# pid_driver.net
KiCad netlist of a schematic drawn in EAGLE
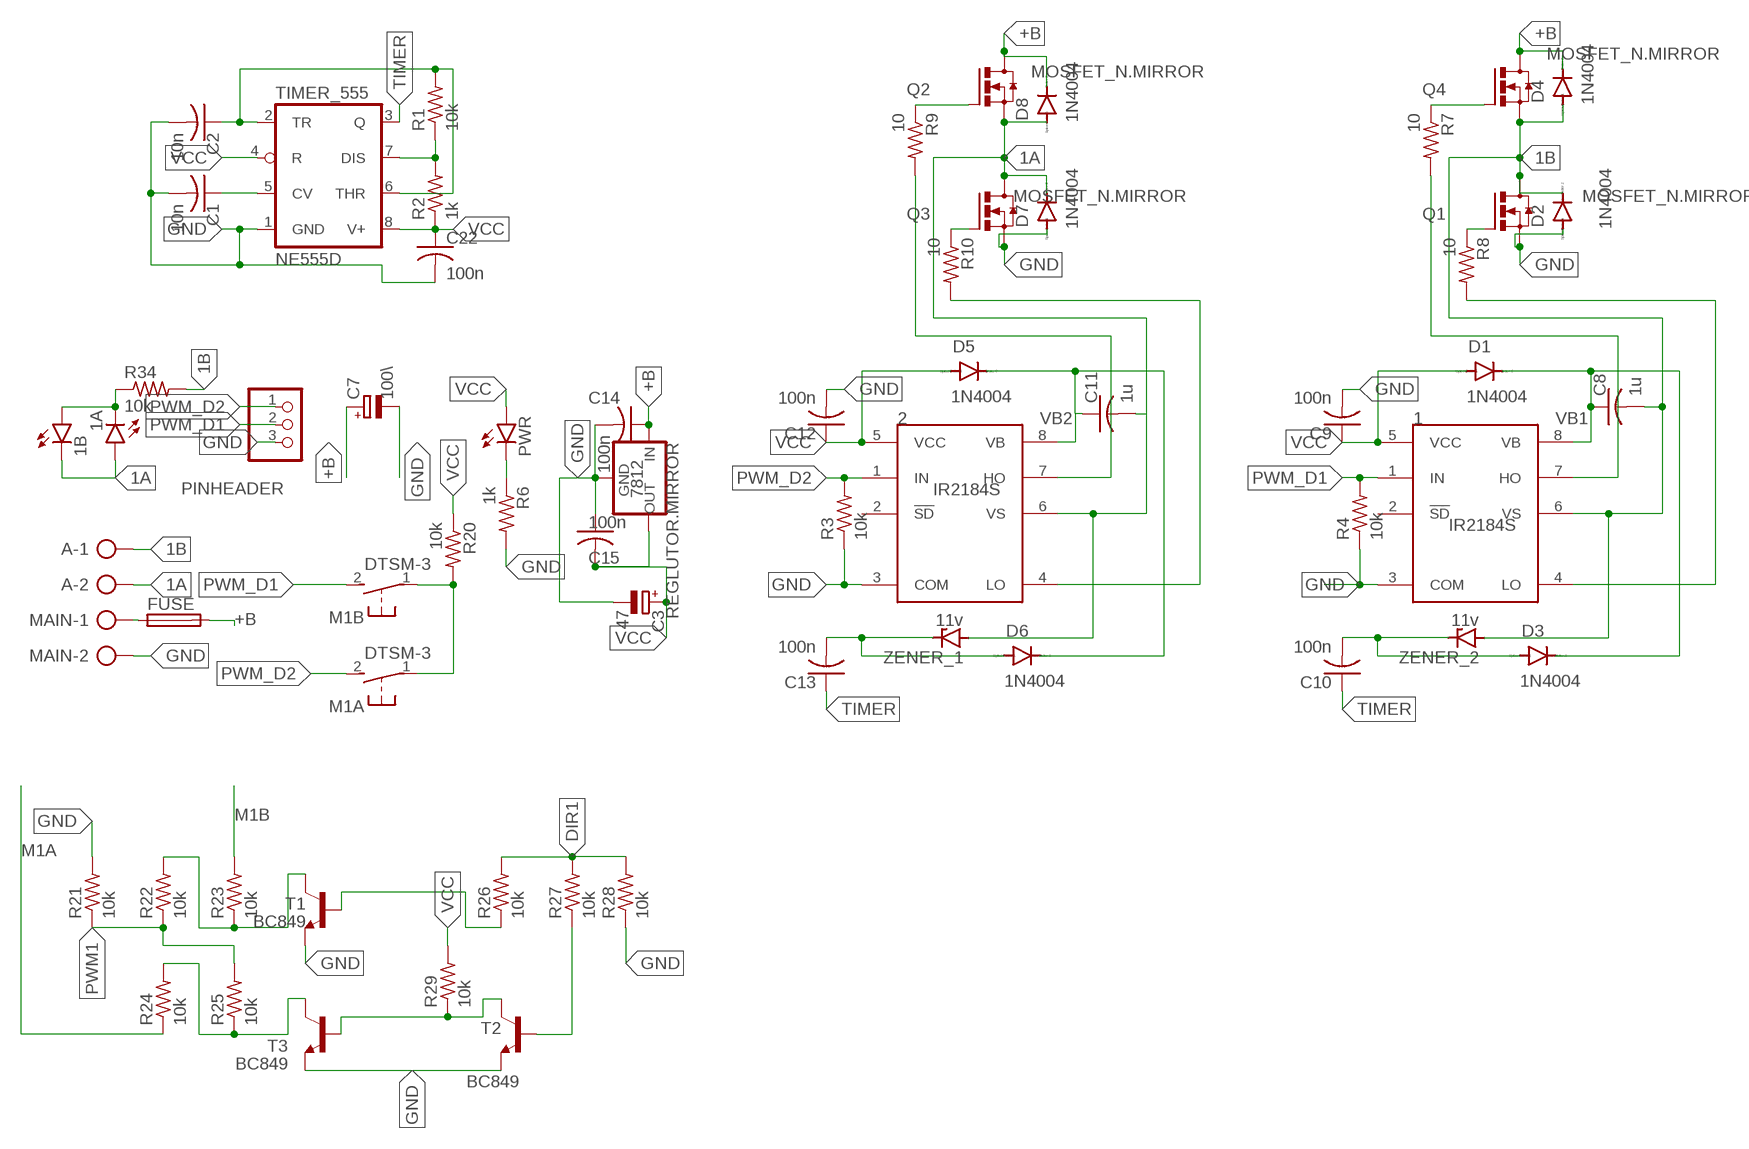
[diagram p0: schematic, sheet 1]
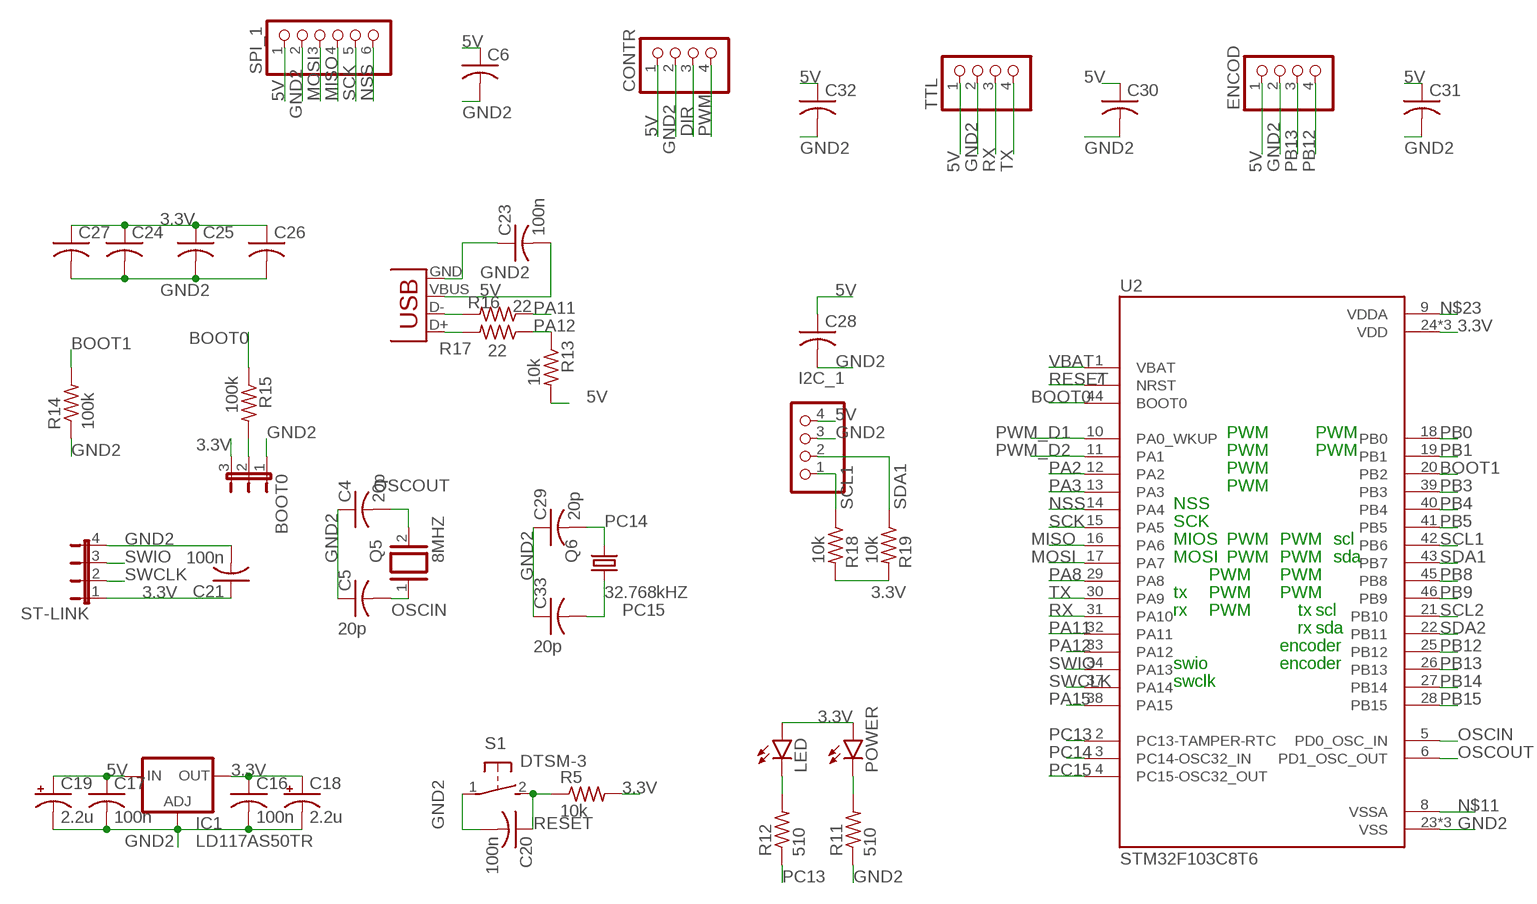
[diagram p1: schematic, sheet 2]

(export (version "E")
  (design (tool "Eeschema 10.0.6"))
  (components
    (comp (ref "BOOT0")
      (value "JP2E")
      (footprint "eagle-import:JP2")
      (libsource (lib "eagle-import") (part "JP2E"))
    )
    (comp (ref "C4")
      (value "20p")
      (footprint "eagle-import:C1206")
      (libsource (lib "eagle-import") (part "C-USC1206"))
    )
    (comp (ref "C5")
      (value "20p")
      (footprint "eagle-import:C1206")
      (libsource (lib "eagle-import") (part "C-USC1206"))
    )
    (comp (ref "C6")
      (value "C-USC1206")
      (footprint "eagle-import:C1206")
      (libsource (lib "eagle-import") (part "C-USC1206"))
    )
    (comp (ref "C16")
      (value "100n")
      (footprint "eagle-import:C1206")
      (libsource (lib "eagle-import") (part "C-USC1206"))
    )
    (comp (ref "C17")
      (value "100n")
      (footprint "eagle-import:C1206")
      (libsource (lib "eagle-import") (part "C-USC1206"))
    )
    (comp (ref "C18")
      (value "2.2u")
      (footprint "eagle-import:E2-5")
      (libsource (lib "eagle-import") (part "CPOL-USE2-5"))
    )
    (comp (ref "C19")
      (value "2.2u")
      (footprint "eagle-import:E2-5")
      (libsource (lib "eagle-import") (part "CPOL-USE2-5"))
    )
    (comp (ref "C20")
      (value "100n")
      (footprint "eagle-import:C1206")
      (libsource (lib "eagle-import") (part "C-USC1206"))
    )
    (comp (ref "C21")
      (value "100n")
      (footprint "eagle-import:C1206")
      (libsource (lib "eagle-import") (part "C-USC1206"))
    )
    (comp (ref "C23")
      (value "100n")
      (footprint "eagle-import:C1206")
      (libsource (lib "eagle-import") (part "C-USC1206"))
    )
    (comp (ref "C24")
      (value "C-USC1206")
      (footprint "eagle-import:C1206")
      (libsource (lib "eagle-import") (part "C-USC1206"))
    )
    (comp (ref "C25")
      (value "C-USC1206")
      (footprint "eagle-import:C1206")
      (libsource (lib "eagle-import") (part "C-USC1206"))
    )
    (comp (ref "C26")
      (value "C-USC1206")
      (footprint "eagle-import:C1206")
      (libsource (lib "eagle-import") (part "C-USC1206"))
    )
    (comp (ref "C27")
      (value "C-USC1206")
      (footprint "eagle-import:C1206")
      (libsource (lib "eagle-import") (part "C-USC1206"))
    )
    (comp (ref "C28")
      (value "C-USC1206")
      (footprint "eagle-import:C1206")
      (libsource (lib "eagle-import") (part "C-USC1206"))
    )
    (comp (ref "C29")
      (value "20p")
      (footprint "eagle-import:C1206")
      (libsource (lib "eagle-import") (part "C-USC1206"))
    )
    (comp (ref "C30")
      (value "C-USC1206")
      (footprint "eagle-import:C1206")
      (libsource (lib "eagle-import") (part "C-USC1206"))
    )
    (comp (ref "C31")
      (value "C-USC1206")
      (footprint "eagle-import:C1206")
      (libsource (lib "eagle-import") (part "C-USC1206"))
    )
    (comp (ref "C32")
      (value "C-USC1206")
      (footprint "eagle-import:C1206")
      (libsource (lib "eagle-import") (part "C-USC1206"))
    )
    (comp (ref "C33")
      (value "20p")
      (footprint "eagle-import:C1206")
      (libsource (lib "eagle-import") (part "C-USC1206"))
    )
    (comp (ref "CONTR")
      (value "PINHD-1X4")
      (footprint "eagle-import:1X04")
      (libsource (lib "eagle-import") (part "PINHD-1X4"))
    )
    (comp (ref "ENCOD")
      (value "PINHD-1X4")
      (footprint "eagle-import:1X04")
      (libsource (lib "eagle-import") (part "PINHD-1X4"))
    )
    (comp (ref "I2C_1")
      (value "PINHD-1X4")
      (footprint "eagle-import:1X04")
      (libsource (lib "eagle-import") (part "pinhead_325_PINHD-1X4"))
    )
    (comp (ref "IC1")
      (value "LD117AS50TR")
      (footprint "eagle-import:SOT223")
      (libsource (lib "eagle-import") (part "LD117A?S50TR"))
    )
    (comp (ref "LED")
      (value "LEDCHIPLED_1206")
      (footprint "eagle-import:CHIPLED_1206")
      (libsource (lib "eagle-import") (part "LEDCHIPLED_1206"))
    )
    (comp (ref "POWER")
      (value "LEDCHIPLED_1206")
      (footprint "eagle-import:CHIPLED_1206")
      (libsource (lib "eagle-import") (part "LEDCHIPLED_1206"))
    )
    (comp (ref "Q5")
      (value "8MHZ")
      (footprint "eagle-import:QS")
      (libsource (lib "eagle-import") (part "XTAL/S"))
    )
    (comp (ref "Q6")
      (value "32.768kHZ")
      (footprint "eagle-import:TC26H")
      (libsource (lib "eagle-import") (part "CRYSTALTC26H"))
    )
    (comp (ref "R5")
      (value "10k")
      (footprint "eagle-import:R1206")
      (libsource (lib "eagle-import") (part "R-US_R1206"))
    )
    (comp (ref "R11")
      (value "510")
      (footprint "eagle-import:R1206")
      (libsource (lib "eagle-import") (part "R-US_R1206"))
    )
    (comp (ref "R12")
      (value "510")
      (footprint "eagle-import:R1206")
      (libsource (lib "eagle-import") (part "R-US_R1206"))
    )
    (comp (ref "R13")
      (value "10k")
      (footprint "eagle-import:R1206")
      (libsource (lib "eagle-import") (part "R-US_R1206"))
    )
    (comp (ref "R14")
      (value "100k")
      (footprint "eagle-import:R1206")
      (libsource (lib "eagle-import") (part "R-US_R1206"))
    )
    (comp (ref "R15")
      (value "100k")
      (footprint "eagle-import:R1206")
      (libsource (lib "eagle-import") (part "R-US_R1206"))
    )
    (comp (ref "R16")
      (value "22")
      (footprint "eagle-import:R1206")
      (libsource (lib "eagle-import") (part "R-US_R1206"))
    )
    (comp (ref "R17")
      (value "22")
      (footprint "eagle-import:R1206")
      (libsource (lib "eagle-import") (part "R-US_R1206"))
    )
    (comp (ref "R18")
      (value "10k")
      (footprint "eagle-import:R1206")
      (libsource (lib "eagle-import") (part "R-US_R1206"))
    )
    (comp (ref "R19")
      (value "10k")
      (footprint "eagle-import:R1206")
      (libsource (lib "eagle-import") (part "R-US_R1206"))
    )
    (comp (ref "S1")
      (value "DTSM-3")
      (footprint "eagle-import:DTSM-3")
      (libsource (lib "eagle-import") (part "DTSM-3"))
    )
    (comp (ref "SPI_1")
      (value "PINHD-1X6")
      (footprint "eagle-import:1X06")
      (libsource (lib "eagle-import") (part "PINHD-1X6"))
    )
    (comp (ref "ST-LINK")
      (value "JP4E")
      (footprint "eagle-import:JP4")
      (libsource (lib "eagle-import") (part "JP4E"))
    )
    (comp (ref "TTL")
      (value "PINHD-1X4")
      (footprint "eagle-import:1X04")
      (libsource (lib "eagle-import") (part "PINHD-1X4"))
    )
    (comp (ref "U2")
      (value "STM32F103C8T6")
      (footprint "eagle-import:QFP50P900X900X160-48N")
      (fields (field (name "MF") "STMicroelectronics"))
      (libsource (lib "eagle-import") (part "STM32F103C8T6"))
    )
    (comp (ref "X1")
      (value "USB-MB-S")
      (footprint "eagle-import:USB-MB-S")
      (libsource (lib "eagle-import") (part "USB-MB-S"))
    )
    (comp (ref "1")
      (value "IR2184S")
      (footprint "eagle-import:SO08")
      (libsource (lib "eagle-import") (part "IR2184S"))
    )
    (comp (ref "1A")
      (value "LEDCHIPLED_1206")
      (footprint "eagle-import:CHIPLED_1206")
      (libsource (lib "eagle-import") (part "LEDCHIPLED_1206"))
    )
    (comp (ref "1B")
      (value "LEDCHIPLED_1206")
      (footprint "eagle-import:CHIPLED_1206")
      (libsource (lib "eagle-import") (part "LEDCHIPLED_1206"))
    )
    (comp (ref "2")
      (value "IR2184S")
      (footprint "eagle-import:SO08")
      (libsource (lib "eagle-import") (part "IR2184S"))
    )
    (comp (ref "7812")
      (value "REGLUTOR.MIRROR")
      (footprint "eagle-import:78XXL.MIRROR")
      (libsource (lib "eagle-import") (part "REGLUTOR.MIRROR"))
    )
    (comp (ref "A")
      (value "AK300/22")
      (footprint "eagle-import:XTALRR488W60L1090T465H350B")
      (libsource (lib "eagle-import") (part "AK300/22"))
    )
    (comp (ref "C1")
      (value "10n")
      (footprint "eagle-import:C1206K")
      (libsource (lib "eagle-import") (part "C-USC1206K"))
    )
    (comp (ref "C2")
      (value "10n")
      (footprint "eagle-import:C1206K")
      (libsource (lib "eagle-import") (part "C-USC1206K"))
    )
    (comp (ref "C3")
      (value "47")
      (footprint "eagle-import:E5-10,5")
      (libsource (lib "eagle-import") (part "CPOL-EUE5-10.5"))
    )
    (comp (ref "C7")
      (value "100\\")
      (footprint "eagle-import:E5-10,5")
      (libsource (lib "eagle-import") (part "CPOL-EUE5-10.5"))
    )
    (comp (ref "C8")
      (value "1u")
      (footprint "eagle-import:C1206K")
      (libsource (lib "eagle-import") (part "C-USC1206K"))
    )
    (comp (ref "C9")
      (value "100n")
      (footprint "eagle-import:C1206K")
      (libsource (lib "eagle-import") (part "C-USC1206K"))
    )
    (comp (ref "C10")
      (value "100n")
      (footprint "eagle-import:C1206K")
      (libsource (lib "eagle-import") (part "C-USC1206K"))
    )
    (comp (ref "C11")
      (value "1u")
      (footprint "eagle-import:C1206K")
      (libsource (lib "eagle-import") (part "C-USC1206K"))
    )
    (comp (ref "C12")
      (value "100n")
      (footprint "eagle-import:C1206K")
      (libsource (lib "eagle-import") (part "C-USC1206K"))
    )
    (comp (ref "C13")
      (value "100n")
      (footprint "eagle-import:C1206K")
      (libsource (lib "eagle-import") (part "C-USC1206K"))
    )
    (comp (ref "C14")
      (value "100n")
      (footprint "eagle-import:C1206K")
      (libsource (lib "eagle-import") (part "C-USC1206K"))
    )
    (comp (ref "C15")
      (value "100n")
      (footprint "eagle-import:C1206K")
      (libsource (lib "eagle-import") (part "C-USC1206K"))
    )
    (comp (ref "C22")
      (value "100n")
      (footprint "eagle-import:C1206K")
      (libsource (lib "eagle-import") (part "C-USC1206K"))
    )
    (comp (ref "D1")
      (value "1N4004")
      (footprint "eagle-import:DO41-10")
      (libsource (lib "eagle-import") (part "1N4004"))
    )
    (comp (ref "D2")
      (value "1N4004")
      (footprint "eagle-import:DO41-10")
      (libsource (lib "eagle-import") (part "1N4004"))
    )
    (comp (ref "D3")
      (value "1N4004")
      (footprint "eagle-import:DO41-10")
      (libsource (lib "eagle-import") (part "1N4004"))
    )
    (comp (ref "D4")
      (value "1N4004")
      (footprint "eagle-import:DO41-10")
      (libsource (lib "eagle-import") (part "1N4004"))
    )
    (comp (ref "D5")
      (value "1N4004")
      (footprint "eagle-import:DO41-10")
      (libsource (lib "eagle-import") (part "1N4004"))
    )
    (comp (ref "D6")
      (value "1N4004")
      (footprint "eagle-import:DO41-10")
      (libsource (lib "eagle-import") (part "1N4004"))
    )
    (comp (ref "D7")
      (value "1N4004")
      (footprint "eagle-import:DO41-10")
      (libsource (lib "eagle-import") (part "1N4004"))
    )
    (comp (ref "D8")
      (value "1N4004")
      (footprint "eagle-import:DO41-10")
      (libsource (lib "eagle-import") (part "1N4004"))
    )
    (comp (ref "FUSE")
      (value "FUSE_HOLDER")
      (footprint "eagle-import:SH22,5A")
      (libsource (lib "eagle-import") (part "FUSE_HOLDER"))
    )
    (comp (ref "M1A")
      (value "DTSM-3")
      (footprint "eagle-import:DTSM-3")
      (libsource (lib "eagle-import") (part "DTSM-3"))
    )
    (comp (ref "M1B")
      (value "DTSM-3")
      (footprint "eagle-import:DTSM-3")
      (libsource (lib "eagle-import") (part "DTSM-3"))
    )
    (comp (ref "MAIN")
      (value "AK300/22")
      (footprint "eagle-import:XTALRR488W60L1090T465H350B")
      (libsource (lib "eagle-import") (part "AK300/22"))
    )
    (comp (ref "PINHEADER")
      (value "PINHD-1X3")
      (footprint "eagle-import:1X03")
      (libsource (lib "eagle-import") (part "PINHD-1X3"))
    )
    (comp (ref "PWR")
      (value "LEDCHIPLED_1206")
      (footprint "eagle-import:CHIPLED_1206")
      (libsource (lib "eagle-import") (part "LEDCHIPLED_1206"))
    )
    (comp (ref "Q1")
      (value "MOSFET_N.MIRROR")
      (footprint "eagle-import:TO220.MIRROR")
      (libsource (lib "eagle-import") (part "MOSFET_N.MIRROR"))
    )
    (comp (ref "Q2")
      (value "MOSFET_N.MIRROR")
      (footprint "eagle-import:TO220.MIRROR")
      (libsource (lib "eagle-import") (part "MOSFET_N.MIRROR"))
    )
    (comp (ref "Q3")
      (value "MOSFET_N.MIRROR")
      (footprint "eagle-import:TO220.MIRROR")
      (libsource (lib "eagle-import") (part "MOSFET_N.MIRROR"))
    )
    (comp (ref "Q4")
      (value "MOSFET_N.MIRROR")
      (footprint "eagle-import:TO220.MIRROR")
      (libsource (lib "eagle-import") (part "MOSFET_N.MIRROR"))
    )
    (comp (ref "R1")
      (value "10k")
      (footprint "eagle-import:M1206")
      (libsource (lib "eagle-import") (part "R-US_M1206"))
    )
    (comp (ref "R2")
      (value "1k")
      (footprint "eagle-import:M1206")
      (libsource (lib "eagle-import") (part "R-US_M1206"))
    )
    (comp (ref "R3")
      (value "10k")
      (footprint "eagle-import:M1206")
      (libsource (lib "eagle-import") (part "R-US_M1206"))
    )
    (comp (ref "R4")
      (value "10k")
      (footprint "eagle-import:M1206")
      (libsource (lib "eagle-import") (part "R-US_M1206"))
    )
    (comp (ref "R6")
      (value "1k")
      (footprint "eagle-import:M1206")
      (libsource (lib "eagle-import") (part "R-US_M1206"))
    )
    (comp (ref "R7")
      (value "10")
      (footprint "eagle-import:M1206")
      (libsource (lib "eagle-import") (part "R-US_M1206"))
    )
    (comp (ref "R8")
      (value "10")
      (footprint "eagle-import:M1206")
      (libsource (lib "eagle-import") (part "R-US_M1206"))
    )
    (comp (ref "R9")
      (value "10")
      (footprint "eagle-import:M1206")
      (libsource (lib "eagle-import") (part "R-US_M1206"))
    )
    (comp (ref "R10")
      (value "10")
      (footprint "eagle-import:M1206")
      (libsource (lib "eagle-import") (part "R-US_M1206"))
    )
    (comp (ref "R20")
      (value "10k")
      (footprint "eagle-import:M1206")
      (libsource (lib "eagle-import") (part "R-US_M1206"))
    )
    (comp (ref "R21")
      (value "10k")
      (footprint "eagle-import:R1206")
      (libsource (lib "eagle-import") (part "R-US_R1206"))
    )
    (comp (ref "R22")
      (value "10k")
      (footprint "eagle-import:R1206")
      (libsource (lib "eagle-import") (part "R-US_R1206"))
    )
    (comp (ref "R23")
      (value "10k")
      (footprint "eagle-import:R1206")
      (libsource (lib "eagle-import") (part "R-US_R1206"))
    )
    (comp (ref "R24")
      (value "10k")
      (footprint "eagle-import:R1206")
      (libsource (lib "eagle-import") (part "R-US_R1206"))
    )
    (comp (ref "R25")
      (value "10k")
      (footprint "eagle-import:R1206")
      (libsource (lib "eagle-import") (part "R-US_R1206"))
    )
    (comp (ref "R26")
      (value "10k")
      (footprint "eagle-import:R1206")
      (libsource (lib "eagle-import") (part "R-US_R1206"))
    )
    (comp (ref "R27")
      (value "10k")
      (footprint "eagle-import:R1206")
      (libsource (lib "eagle-import") (part "R-US_R1206"))
    )
    (comp (ref "R28")
      (value "10k")
      (footprint "eagle-import:R1206")
      (libsource (lib "eagle-import") (part "R-US_R1206"))
    )
    (comp (ref "R29")
      (value "10k")
      (footprint "eagle-import:R1206")
      (libsource (lib "eagle-import") (part "R-US_R1206"))
    )
    (comp (ref "R34")
      (value "10k")
      (footprint "eagle-import:M1206")
      (libsource (lib "eagle-import") (part "R-US_M1206"))
    )
    (comp (ref "T1")
      (value "BC849")
      (footprint "eagle-import:SOT23")
      (libsource (lib "eagle-import") (part "BC849"))
    )
    (comp (ref "T2")
      (value "BC849")
      (footprint "eagle-import:SOT23")
      (libsource (lib "eagle-import") (part "BC849"))
    )
    (comp (ref "T3")
      (value "BC849")
      (footprint "eagle-import:SOT23")
      (libsource (lib "eagle-import") (part "BC849"))
    )
    (comp (ref "TIMER_555")
      (value "NE555D")
      (footprint "eagle-import:SO08")
      (libsource (lib "eagle-import") (part "555DNE"))
    )
    (comp (ref "ZENER_1")
      (value "11v")
      (footprint "eagle-import:SOD81")
      (libsource (lib "eagle-import") (part "BZD23"))
    )
    (comp (ref "ZENER_2")
      (value "11v")
      (footprint "eagle-import:SOD81")
      (libsource (lib "eagle-import") (part "BZD23"))
    )
  )
  (nets
    (net (code "1") (name "+B") (class "Default")
      (node (ref "7812") (pin "IN") (pinfunction "IN_IN") (pintype "input"))
      (node (ref "C14") (pin "1") (pinfunction "1_1") (pintype "passive"))
      (node (ref "C7") (pin "+") (pinfunction "+_+") (pintype "passive"))
      (node (ref "D4") (pin "C") (pinfunction "C_C") (pintype "passive"))
      (node (ref "D8") (pin "C") (pinfunction "C_C") (pintype "passive"))
      (node (ref "FUSE") (pin "2") (pinfunction "2_2") (pintype "passive"))
      (node (ref "Q2") (pin "D") (pinfunction "D_D") (pintype "passive"))
      (node (ref "Q4") (pin "D") (pinfunction "D_D") (pintype "passive"))
    )
    (net (code "2") (name "1A") (class "Default")
      (node (ref "1A") (pin "A") (pinfunction "A_A") (pintype "passive"))
      (node (ref "1B") (pin "C") (pinfunction "C_C") (pintype "passive"))
      (node (ref "2") (pin "6") (pinfunction "VS_6") (pintype "power_in"))
      (node (ref "A") (pin "2") (pinfunction "KL_2") (pintype "passive"))
      (node (ref "C11") (pin "2") (pinfunction "2_2") (pintype "passive"))
      (node (ref "D7") (pin "C") (pinfunction "C_C") (pintype "passive"))
      (node (ref "D8") (pin "A") (pinfunction "A_A") (pintype "passive"))
      (node (ref "Q2") (pin "S") (pinfunction "S_S") (pintype "passive"))
      (node (ref "Q3") (pin "D") (pinfunction "D_D") (pintype "passive"))
      (node (ref "ZENER_1") (pin "A") (pinfunction "A_A") (pintype "passive"))
    )
    (net (code "3") (name "1B") (class "Default")
      (node (ref "1") (pin "6") (pinfunction "VS_6") (pintype "power_in"))
      (node (ref "A") (pin "1") (pinfunction "KL_1") (pintype "passive"))
      (node (ref "C8") (pin "2") (pinfunction "2_2") (pintype "passive"))
      (node (ref "D2") (pin "C") (pinfunction "C_C") (pintype "passive"))
      (node (ref "D4") (pin "A") (pinfunction "A_A") (pintype "passive"))
      (node (ref "Q1") (pin "D") (pinfunction "D_D") (pintype "passive"))
      (node (ref "Q4") (pin "S") (pinfunction "S_S") (pintype "passive"))
      (node (ref "R34") (pin "2") (pinfunction "2_2") (pintype "passive"))
      (node (ref "ZENER_2") (pin "A") (pinfunction "A_A") (pintype "passive"))
    )
    (net (code "4") (name "3.3V") (class "Default")
      (node (ref "BOOT0") (pin "3") (pinfunction "3_3") (pintype "passive"))
      (node (ref "C16") (pin "1") (pinfunction "1_1") (pintype "passive"))
      (node (ref "C18") (pin "+") (pinfunction "+_+") (pintype "passive"))
      (node (ref "C21") (pin "1") (pinfunction "1_1") (pintype "passive"))
      (node (ref "C24") (pin "1") (pinfunction "1_1") (pintype "passive"))
      (node (ref "C25") (pin "1") (pinfunction "1_1") (pintype "passive"))
      (node (ref "C26") (pin "1") (pinfunction "1_1") (pintype "passive"))
      (node (ref "C27") (pin "1") (pinfunction "1_1") (pintype "passive"))
      (node (ref "IC1") (pin "4") (pinfunction "OUT_4") (pintype "passive"))
      (node (ref "LED") (pin "A") (pinfunction "A_A") (pintype "passive"))
      (node (ref "POWER") (pin "A") (pinfunction "A_A") (pintype "passive"))
      (node (ref "R18") (pin "2") (pinfunction "2_2") (pintype "passive"))
      (node (ref "R19") (pin "2") (pinfunction "2_2") (pintype "passive"))
      (node (ref "R5") (pin "2") (pinfunction "2_2") (pintype "passive"))
      (node (ref "ST-LINK") (pin "1") (pinfunction "1_1") (pintype "passive"))
      (node (ref "U2") (pin "24") (pinfunction "VDD_24") (pintype "power_in"))
      (node (ref "U2") (pin "36") (pinfunction "VDD_36") (pintype "power_in"))
      (node (ref "U2") (pin "48") (pinfunction "VDD_48") (pintype "power_in"))
    )
    (net (code "5") (name "5V") (class "Default")
      (node (ref "C17") (pin "1") (pinfunction "1_1") (pintype "passive"))
      (node (ref "C19") (pin "+") (pinfunction "+_+") (pintype "passive"))
      (node (ref "C23") (pin "2") (pinfunction "2_2") (pintype "passive"))
      (node (ref "C28") (pin "1") (pinfunction "1_1") (pintype "passive"))
      (node (ref "C30") (pin "1") (pinfunction "1_1") (pintype "passive"))
      (node (ref "C31") (pin "1") (pinfunction "1_1") (pintype "passive"))
      (node (ref "C32") (pin "1") (pinfunction "1_1") (pintype "passive"))
      (node (ref "C6") (pin "1") (pinfunction "1_1") (pintype "passive"))
      (node (ref "CONTR") (pin "1") (pinfunction "1_1") (pintype "passive"))
      (node (ref "ENCOD") (pin "1") (pinfunction "1_1") (pintype "passive"))
      (node (ref "I2C_1") (pin "4") (pinfunction "4_4") (pintype "passive"))
      (node (ref "IC1") (pin "3") (pinfunction "IN_3") (pintype "input"))
      (node (ref "R13") (pin "2") (pinfunction "2_2") (pintype "passive"))
      (node (ref "SPI_1") (pin "1") (pinfunction "1_1") (pintype "passive"))
      (node (ref "TTL") (pin "1") (pinfunction "1_1") (pintype "passive"))
      (node (ref "X1") (pin "VBUS") (pinfunction "VBUS_VBUS") (pintype "bidirectional"))
    )
    (net (code "6") (name "BOOT0") (class "Default")
      (node (ref "R15") (pin "1") (pinfunction "1_1") (pintype "passive"))
      (node (ref "U2") (pin "44") (pinfunction "BOOT0_44") (pintype "input"))
    )
    (net (code "7") (name "BOOT1") (class "Default")
      (node (ref "R14") (pin "2") (pinfunction "2_2") (pintype "passive"))
      (node (ref "U2") (pin "20") (pinfunction "PB2_20") (pintype "bidirectional"))
    )
    (net (code "8") (name "DIR") (class "Default")
      (node (ref "CONTR") (pin "3") (pinfunction "3_3") (pintype "passive"))
    )
    (net (code "9") (name "DIR1") (class "Default")
      (node (ref "R26") (pin "2") (pinfunction "2_2") (pintype "passive"))
      (node (ref "R27") (pin "2") (pinfunction "2_2") (pintype "passive"))
      (node (ref "R28") (pin "2") (pinfunction "2_2") (pintype "passive"))
    )
    (net (code "10") (name "GND") (class "Default")
      (node (ref "1") (pin "3") (pinfunction "COM_3") (pintype "power_in"))
      (node (ref "2") (pin "3") (pinfunction "COM_3") (pintype "power_in"))
      (node (ref "7812") (pin "GND") (pinfunction "GND_GND") (pintype "input"))
      (node (ref "C1") (pin "2") (pinfunction "2_2") (pintype "passive"))
      (node (ref "C12") (pin "2") (pinfunction "2_2") (pintype "passive"))
      (node (ref "C14") (pin "2") (pinfunction "2_2") (pintype "passive"))
      (node (ref "C15") (pin "1") (pinfunction "1_1") (pintype "passive"))
      (node (ref "C2") (pin "2") (pinfunction "2_2") (pintype "passive"))
      (node (ref "C22") (pin "2") (pinfunction "2_2") (pintype "passive"))
      (node (ref "C3") (pin "-") (pinfunction "-_-") (pintype "passive"))
      (node (ref "C7") (pin "-") (pinfunction "-_-") (pintype "passive"))
      (node (ref "C9") (pin "2") (pinfunction "2_2") (pintype "passive"))
      (node (ref "D2") (pin "A") (pinfunction "A_A") (pintype "passive"))
      (node (ref "D7") (pin "A") (pinfunction "A_A") (pintype "passive"))
      (node (ref "MAIN") (pin "2") (pinfunction "KL_2") (pintype "passive"))
      (node (ref "PINHEADER") (pin "3") (pinfunction "3_3") (pintype "passive"))
      (node (ref "Q1") (pin "S") (pinfunction "S_S") (pintype "passive"))
      (node (ref "Q3") (pin "S") (pinfunction "S_S") (pintype "passive"))
      (node (ref "R21") (pin "2") (pinfunction "2_2") (pintype "passive"))
      (node (ref "R28") (pin "1") (pinfunction "1_1") (pintype "passive"))
      (node (ref "R3") (pin "1") (pinfunction "1_1") (pintype "passive"))
      (node (ref "R4") (pin "1") (pinfunction "1_1") (pintype "passive"))
      (node (ref "R6") (pin "2") (pinfunction "2_2") (pintype "passive"))
      (node (ref "T1") (pin "2") (pinfunction "E_2") (pintype "passive"))
      (node (ref "T2") (pin "2") (pinfunction "E_2") (pintype "passive"))
      (node (ref "T3") (pin "2") (pinfunction "E_2") (pintype "passive"))
      (node (ref "TIMER_555") (pin "1") (pinfunction "GND_1") (pintype "power_in"))
    )
    (net (code "11") (name "GND2") (class "Default")
      (node (ref "BOOT0") (pin "1") (pinfunction "1_1") (pintype "passive"))
      (node (ref "C16") (pin "2") (pinfunction "2_2") (pintype "passive"))
      (node (ref "C17") (pin "2") (pinfunction "2_2") (pintype "passive"))
      (node (ref "C18") (pin "-") (pinfunction "-_-") (pintype "passive"))
      (node (ref "C19") (pin "-") (pinfunction "-_-") (pintype "passive"))
      (node (ref "C20") (pin "2") (pinfunction "2_2") (pintype "passive"))
      (node (ref "C21") (pin "2") (pinfunction "2_2") (pintype "passive"))
      (node (ref "C23") (pin "1") (pinfunction "1_1") (pintype "passive"))
      (node (ref "C24") (pin "2") (pinfunction "2_2") (pintype "passive"))
      (node (ref "C25") (pin "2") (pinfunction "2_2") (pintype "passive"))
      (node (ref "C26") (pin "2") (pinfunction "2_2") (pintype "passive"))
      (node (ref "C27") (pin "2") (pinfunction "2_2") (pintype "passive"))
      (node (ref "C28") (pin "2") (pinfunction "2_2") (pintype "passive"))
      (node (ref "C29") (pin "1") (pinfunction "1_1") (pintype "passive"))
      (node (ref "C30") (pin "2") (pinfunction "2_2") (pintype "passive"))
      (node (ref "C31") (pin "2") (pinfunction "2_2") (pintype "passive"))
      (node (ref "C32") (pin "2") (pinfunction "2_2") (pintype "passive"))
      (node (ref "C33") (pin "1") (pinfunction "1_1") (pintype "passive"))
      (node (ref "C4") (pin "1") (pinfunction "1_1") (pintype "passive"))
      (node (ref "C5") (pin "1") (pinfunction "1_1") (pintype "passive"))
      (node (ref "C6") (pin "2") (pinfunction "2_2") (pintype "passive"))
      (node (ref "CONTR") (pin "2") (pinfunction "2_2") (pintype "passive"))
      (node (ref "ENCOD") (pin "2") (pinfunction "2_2") (pintype "passive"))
      (node (ref "I2C_1") (pin "3") (pinfunction "3_3") (pintype "passive"))
      (node (ref "IC1") (pin "1") (pinfunction "ADJ_1") (pintype "input"))
      (node (ref "R11") (pin "1") (pinfunction "1_1") (pintype "passive"))
      (node (ref "R14") (pin "1") (pinfunction "1_1") (pintype "passive"))
      (node (ref "S1") (pin "1") (pinfunction "1_1") (pintype "passive"))
      (node (ref "SPI_1") (pin "2") (pinfunction "2_2") (pintype "passive"))
      (node (ref "ST-LINK") (pin "4") (pinfunction "4_4") (pintype "passive"))
      (node (ref "TTL") (pin "2") (pinfunction "2_2") (pintype "passive"))
      (node (ref "U2") (pin "23") (pinfunction "VSS_23") (pintype "power_in"))
      (node (ref "U2") (pin "35") (pinfunction "VSS_35") (pintype "power_in"))
      (node (ref "U2") (pin "47") (pinfunction "VSS_47") (pintype "power_in"))
      (node (ref "X1") (pin "GND") (pinfunction "GND_GND") (pintype "bidirectional"))
    )
    (net (code "12") (name "M1A") (class "Default")
      (node (ref "R24") (pin "1") (pinfunction "1_1") (pintype "passive"))
    )
    (net (code "13") (name "M1B") (class "Default")
      (node (ref "R23") (pin "2") (pinfunction "2_2") (pintype "passive"))
    )
    (net (code "14") (name "MISO") (class "Default")
      (node (ref "SPI_1") (pin "4") (pinfunction "4_4") (pintype "passive"))
      (node (ref "U2") (pin "16") (pinfunction "PA6_16") (pintype "bidirectional"))
    )
    (net (code "15") (name "MOSI") (class "Default")
      (node (ref "SPI_1") (pin "3") (pinfunction "3_3") (pintype "passive"))
      (node (ref "U2") (pin "17") (pinfunction "PA7_17") (pintype "bidirectional"))
    )
    (net (code "16") (name "N$11") (class "Default")
      (node (ref "U2") (pin "8") (pinfunction "VSSA_8") (pintype "power_in"))
    )
    (net (code "17") (name "N$23") (class "Default")
      (node (ref "U2") (pin "9") (pinfunction "VDDA_9") (pintype "power_in"))
    )
    (net (code "18") (name "NSS") (class "Default")
      (node (ref "SPI_1") (pin "6") (pinfunction "6_6") (pintype "passive"))
      (node (ref "U2") (pin "14") (pinfunction "PA4_14") (pintype "bidirectional"))
    )
    (net (code "19") (name "Net-(1-HO)") (class "Default")
      (node (ref "1") (pin "7") (pinfunction "HO_7") (pintype "output"))
      (node (ref "R7") (pin "2") (pinfunction "2_2") (pintype "passive"))
    )
    (net (code "20") (name "Net-(1-LO)") (class "Default")
      (node (ref "1") (pin "4") (pinfunction "LO_4") (pintype "output"))
      (node (ref "R8") (pin "2") (pinfunction "2_2") (pintype "passive"))
    )
    (net (code "21") (name "Net-(1A-PadC)") (class "Default")
      (node (ref "1A") (pin "C") (pinfunction "C_C") (pintype "passive"))
      (node (ref "1B") (pin "A") (pinfunction "A_A") (pintype "passive"))
      (node (ref "R34") (pin "1") (pinfunction "1_1") (pintype "passive"))
    )
    (net (code "22") (name "Net-(2-HO)") (class "Default")
      (node (ref "2") (pin "7") (pinfunction "HO_7") (pintype "output"))
      (node (ref "R9") (pin "2") (pinfunction "2_2") (pintype "passive"))
    )
    (net (code "23") (name "Net-(2-LO)") (class "Default")
      (node (ref "2") (pin "4") (pinfunction "LO_4") (pintype "output"))
      (node (ref "R10") (pin "2") (pinfunction "2_2") (pintype "passive"))
    )
    (net (code "24") (name "Net-(BOOT0-Pad2)") (class "Default")
      (node (ref "BOOT0") (pin "2") (pinfunction "2_2") (pintype "passive"))
      (node (ref "R15") (pin "2") (pinfunction "2_2") (pintype "passive"))
    )
    (net (code "25") (name "Net-(C10-Pad2)") (class "Default")
      (node (ref "C10") (pin "2") (pinfunction "2_2") (pintype "passive"))
      (node (ref "D3") (pin "A") (pinfunction "A_A") (pintype "passive"))
      (node (ref "ZENER_2") (pin "C") (pinfunction "C_C") (pintype "passive"))
    )
    (net (code "26") (name "Net-(C13-Pad2)") (class "Default")
      (node (ref "C13") (pin "2") (pinfunction "2_2") (pintype "passive"))
      (node (ref "D6") (pin "A") (pinfunction "A_A") (pintype "passive"))
      (node (ref "ZENER_1") (pin "C") (pinfunction "C_C") (pintype "passive"))
    )
    (net (code "27") (name "Net-(LED-PadC)") (class "Default")
      (node (ref "LED") (pin "C") (pinfunction "C_C") (pintype "passive"))
      (node (ref "R12") (pin "2") (pinfunction "2_2") (pintype "passive"))
    )
    (net (code "28") (name "Net-(M1A-Pad1)") (class "Default")
      (node (ref "M1A") (pin "1") (pinfunction "1_1") (pintype "passive"))
      (node (ref "M1B") (pin "1") (pinfunction "1_1") (pintype "passive"))
      (node (ref "R20") (pin "2") (pinfunction "2_2") (pintype "passive"))
    )
    (net (code "29") (name "Net-(MAINA-KL)") (class "Default")
      (node (ref "FUSE") (pin "1") (pinfunction "1_1") (pintype "passive"))
      (node (ref "MAIN") (pin "1") (pinfunction "KL_1") (pintype "passive"))
    )
    (net (code "30") (name "Net-(POWER-PadC)") (class "Default")
      (node (ref "POWER") (pin "C") (pinfunction "C_C") (pintype "passive"))
      (node (ref "R11") (pin "2") (pinfunction "2_2") (pintype "passive"))
    )
    (net (code "31") (name "Net-(PWR-PadC)") (class "Default")
      (node (ref "PWR") (pin "C") (pinfunction "C_C") (pintype "passive"))
      (node (ref "R6") (pin "1") (pinfunction "1_1") (pintype "passive"))
    )
    (net (code "32") (name "Net-(Q1-PadG)") (class "Default")
      (node (ref "Q1") (pin "G") (pinfunction "G_G") (pintype "passive"))
      (node (ref "R8") (pin "1") (pinfunction "1_1") (pintype "passive"))
    )
    (net (code "33") (name "Net-(Q2-PadG)") (class "Default")
      (node (ref "Q2") (pin "G") (pinfunction "G_G") (pintype "passive"))
      (node (ref "R9") (pin "1") (pinfunction "1_1") (pintype "passive"))
    )
    (net (code "34") (name "Net-(Q3-PadG)") (class "Default")
      (node (ref "Q3") (pin "G") (pinfunction "G_G") (pintype "passive"))
      (node (ref "R10") (pin "1") (pinfunction "1_1") (pintype "passive"))
    )
    (net (code "35") (name "Net-(Q4-PadG)") (class "Default")
      (node (ref "Q4") (pin "G") (pinfunction "G_G") (pintype "passive"))
      (node (ref "R7") (pin "1") (pinfunction "1_1") (pintype "passive"))
    )
    (net (code "36") (name "Net-(R16-Pad2)") (class "Default")
      (node (ref "R16") (pin "2") (pinfunction "2_2") (pintype "passive"))
      (node (ref "X1") (pin "D-") (pinfunction "D-_D-") (pintype "bidirectional"))
    )
    (net (code "37") (name "Net-(R17-Pad2)") (class "Default")
      (node (ref "R17") (pin "2") (pinfunction "2_2") (pintype "passive"))
      (node (ref "X1") (pin "D+") (pinfunction "D+_D+") (pintype "bidirectional"))
    )
    (net (code "38") (name "Net-(T1-B)") (class "Default")
      (node (ref "R26") (pin "1") (pinfunction "1_1") (pintype "passive"))
      (node (ref "T1") (pin "1") (pinfunction "B_1") (pintype "passive"))
    )
    (net (code "39") (name "Net-(T1-C)") (class "Default")
      (node (ref "R22") (pin "2") (pinfunction "2_2") (pintype "passive"))
      (node (ref "R23") (pin "1") (pinfunction "1_1") (pintype "passive"))
      (node (ref "T1") (pin "3") (pinfunction "C_3") (pintype "passive"))
    )
    (net (code "40") (name "Net-(T2-B)") (class "Default")
      (node (ref "R27") (pin "1") (pinfunction "1_1") (pintype "passive"))
      (node (ref "T2") (pin "1") (pinfunction "B_1") (pintype "passive"))
    )
    (net (code "41") (name "Net-(T2-C)") (class "Default")
      (node (ref "R29") (pin "1") (pinfunction "1_1") (pintype "passive"))
      (node (ref "T2") (pin "3") (pinfunction "C_3") (pintype "passive"))
      (node (ref "T3") (pin "1") (pinfunction "B_1") (pintype "passive"))
    )
    (net (code "42") (name "Net-(T3-C)") (class "Default")
      (node (ref "R24") (pin "2") (pinfunction "2_2") (pintype "passive"))
      (node (ref "R25") (pin "1") (pinfunction "1_1") (pintype "passive"))
      (node (ref "T3") (pin "3") (pinfunction "C_3") (pintype "passive"))
    )
    (net (code "43") (name "Net-(TIMER_555-CV)") (class "Default")
      (node (ref "C1") (pin "1") (pinfunction "1_1") (pintype "passive"))
      (node (ref "TIMER_555") (pin "5") (pinfunction "CV_5") (pintype "input"))
    )
    (net (code "44") (name "Net-(TIMER_555-DIS)") (class "Default")
      (node (ref "R1") (pin "1") (pinfunction "1_1") (pintype "passive"))
      (node (ref "R2") (pin "2") (pinfunction "2_2") (pintype "passive"))
      (node (ref "TIMER_555") (pin "7") (pinfunction "DIS_7") (pintype "input"))
    )
    (net (code "45") (name "Net-(TIMER_555-THR)") (class "Default")
      (node (ref "C2") (pin "1") (pinfunction "1_1") (pintype "passive"))
      (node (ref "R1") (pin "2") (pinfunction "2_2") (pintype "passive"))
      (node (ref "TIMER_555") (pin "2") (pinfunction "TR_2") (pintype "input"))
      (node (ref "TIMER_555") (pin "6") (pinfunction "THR_6") (pintype "input"))
    )
    (net (code "46") (name "OSCIN") (class "Default")
      (node (ref "C5") (pin "2") (pinfunction "2_2") (pintype "passive"))
      (node (ref "Q5") (pin "1") (pinfunction "1_1") (pintype "passive"))
      (node (ref "U2") (pin "5") (pinfunction "PD0_OSC_IN_5") (pintype "bidirectional"))
    )
    (net (code "47") (name "OSCOUT") (class "Default")
      (node (ref "C4") (pin "2") (pinfunction "2_2") (pintype "passive"))
      (node (ref "Q5") (pin "2") (pinfunction "2_2") (pintype "passive"))
      (node (ref "U2") (pin "6") (pinfunction "PD1_OSC_OUT_6") (pintype "bidirectional"))
    )
    (net (code "48") (name "PA2") (class "Default")
      (node (ref "U2") (pin "12") (pinfunction "PA2_12") (pintype "bidirectional"))
    )
    (net (code "49") (name "PA3") (class "Default")
      (node (ref "U2") (pin "13") (pinfunction "PA3_13") (pintype "bidirectional"))
    )
    (net (code "50") (name "PA8") (class "Default")
      (node (ref "U2") (pin "29") (pinfunction "PA8_29") (pintype "bidirectional"))
    )
    (net (code "51") (name "PA11") (class "Default")
      (node (ref "R16") (pin "1") (pinfunction "1_1") (pintype "passive"))
      (node (ref "U2") (pin "32") (pinfunction "PA11_32") (pintype "bidirectional"))
    )
    (net (code "52") (name "PA12") (class "Default")
      (node (ref "R13") (pin "1") (pinfunction "1_1") (pintype "passive"))
      (node (ref "R17") (pin "1") (pinfunction "1_1") (pintype "passive"))
      (node (ref "U2") (pin "33") (pinfunction "PA12_33") (pintype "bidirectional"))
    )
    (net (code "53") (name "PA15") (class "Default")
      (node (ref "U2") (pin "38") (pinfunction "PA15_38") (pintype "bidirectional"))
    )
    (net (code "54") (name "PB0") (class "Default")
      (node (ref "U2") (pin "18") (pinfunction "PB0_18") (pintype "bidirectional"))
    )
    (net (code "55") (name "PB1") (class "Default")
      (node (ref "U2") (pin "19") (pinfunction "PB1_19") (pintype "bidirectional"))
    )
    (net (code "56") (name "PB3") (class "Default")
      (node (ref "U2") (pin "39") (pinfunction "PB3_39") (pintype "bidirectional"))
    )
    (net (code "57") (name "PB4") (class "Default")
      (node (ref "U2") (pin "40") (pinfunction "PB4_40") (pintype "bidirectional"))
    )
    (net (code "58") (name "PB5") (class "Default")
      (node (ref "U2") (pin "41") (pinfunction "PB5_41") (pintype "bidirectional"))
    )
    (net (code "59") (name "PB8") (class "Default")
      (node (ref "U2") (pin "45") (pinfunction "PB8_45") (pintype "bidirectional"))
    )
    (net (code "60") (name "PB9") (class "Default")
      (node (ref "U2") (pin "46") (pinfunction "PB9_46") (pintype "bidirectional"))
    )
    (net (code "61") (name "PB12") (class "Default")
      (node (ref "ENCOD") (pin "4") (pinfunction "4_4") (pintype "passive"))
      (node (ref "U2") (pin "25") (pinfunction "PB12_25") (pintype "bidirectional"))
    )
    (net (code "62") (name "PB13") (class "Default")
      (node (ref "ENCOD") (pin "3") (pinfunction "3_3") (pintype "passive"))
      (node (ref "U2") (pin "26") (pinfunction "PB13_26") (pintype "bidirectional"))
    )
    (net (code "63") (name "PB14") (class "Default")
      (node (ref "U2") (pin "27") (pinfunction "PB14_27") (pintype "bidirectional"))
    )
    (net (code "64") (name "PB15") (class "Default")
      (node (ref "U2") (pin "28") (pinfunction "PB15_28") (pintype "bidirectional"))
    )
    (net (code "65") (name "PC13") (class "Default")
      (node (ref "R12") (pin "1") (pinfunction "1_1") (pintype "passive"))
      (node (ref "U2") (pin "2") (pinfunction "PC13-TAMPER-RTC_2") (pintype "bidirectional"))
    )
    (net (code "66") (name "PC14") (class "Default")
      (node (ref "C29") (pin "2") (pinfunction "2_2") (pintype "passive"))
      (node (ref "Q6") (pin "2") (pinfunction "2_2") (pintype "passive"))
      (node (ref "U2") (pin "3") (pinfunction "PC14-OSC32_IN_3") (pintype "bidirectional"))
    )
    (net (code "67") (name "PC15") (class "Default")
      (node (ref "C33") (pin "2") (pinfunction "2_2") (pintype "passive"))
      (node (ref "Q6") (pin "1") (pinfunction "1_1") (pintype "passive"))
      (node (ref "U2") (pin "4") (pinfunction "PC15-OSC32_OUT_4") (pintype "bidirectional"))
    )
    (net (code "68") (name "PWM") (class "Default")
      (node (ref "CONTR") (pin "4") (pinfunction "4_4") (pintype "passive"))
    )
    (net (code "69") (name "PWM1") (class "Default")
      (node (ref "R21") (pin "1") (pinfunction "1_1") (pintype "passive"))
      (node (ref "R22") (pin "1") (pinfunction "1_1") (pintype "passive"))
      (node (ref "R25") (pin "2") (pinfunction "2_2") (pintype "passive"))
    )
    (net (code "70") (name "PWM_D1") (class "Default")
      (node (ref "1") (pin "1") (pinfunction "IN_1") (pintype "input"))
      (node (ref "M1B") (pin "2") (pinfunction "2_2") (pintype "passive"))
      (node (ref "PINHEADER") (pin "2") (pinfunction "2_2") (pintype "passive"))
      (node (ref "R4") (pin "2") (pinfunction "2_2") (pintype "passive"))
      (node (ref "U2") (pin "10") (pinfunction "PA0_WKUP_10") (pintype "bidirectional"))
    )
    (net (code "71") (name "PWM_D2") (class "Default")
      (node (ref "2") (pin "1") (pinfunction "IN_1") (pintype "input"))
      (node (ref "M1A") (pin "2") (pinfunction "2_2") (pintype "passive"))
      (node (ref "PINHEADER") (pin "1") (pinfunction "1_1") (pintype "passive"))
      (node (ref "R3") (pin "2") (pinfunction "2_2") (pintype "passive"))
      (node (ref "U2") (pin "11") (pinfunction "PA1_11") (pintype "bidirectional"))
    )
    (net (code "72") (name "RESET") (class "Default")
      (node (ref "C20") (pin "1") (pinfunction "1_1") (pintype "passive"))
      (node (ref "R5") (pin "1") (pinfunction "1_1") (pintype "passive"))
      (node (ref "S1") (pin "2") (pinfunction "2_2") (pintype "passive"))
      (node (ref "U2") (pin "7") (pinfunction "NRST_7") (pintype "input"))
    )
    (net (code "73") (name "RX") (class "Default")
      (node (ref "TTL") (pin "3") (pinfunction "3_3") (pintype "passive"))
      (node (ref "U2") (pin "31") (pinfunction "PA10_31") (pintype "bidirectional"))
    )
    (net (code "74") (name "SCK") (class "Default")
      (node (ref "SPI_1") (pin "5") (pinfunction "5_5") (pintype "passive"))
      (node (ref "U2") (pin "15") (pinfunction "PA5_15") (pintype "bidirectional"))
    )
    (net (code "75") (name "SCL1") (class "Default")
      (node (ref "I2C_1") (pin "1") (pinfunction "1_1") (pintype "passive"))
      (node (ref "R18") (pin "1") (pinfunction "1_1") (pintype "passive"))
      (node (ref "U2") (pin "42") (pinfunction "PB6_42") (pintype "bidirectional"))
    )
    (net (code "76") (name "SCL2") (class "Default")
      (node (ref "U2") (pin "21") (pinfunction "PB10_21") (pintype "bidirectional"))
    )
    (net (code "77") (name "SDA1") (class "Default")
      (node (ref "I2C_1") (pin "2") (pinfunction "2_2") (pintype "passive"))
      (node (ref "R19") (pin "1") (pinfunction "1_1") (pintype "passive"))
      (node (ref "U2") (pin "43") (pinfunction "PB7_43") (pintype "bidirectional"))
    )
    (net (code "78") (name "SDA2") (class "Default")
      (node (ref "U2") (pin "22") (pinfunction "PB11_22") (pintype "bidirectional"))
    )
    (net (code "79") (name "SWCLK") (class "Default")
      (node (ref "ST-LINK") (pin "2") (pinfunction "2_2") (pintype "passive"))
      (node (ref "U2") (pin "37") (pinfunction "PA14_37") (pintype "bidirectional"))
    )
    (net (code "80") (name "SWIO") (class "Default")
      (node (ref "ST-LINK") (pin "3") (pinfunction "3_3") (pintype "passive"))
      (node (ref "U2") (pin "34") (pinfunction "PA13_34") (pintype "bidirectional"))
    )
    (net (code "81") (name "TIMER") (class "Default")
      (node (ref "C10") (pin "1") (pinfunction "1_1") (pintype "passive"))
      (node (ref "C13") (pin "1") (pinfunction "1_1") (pintype "passive"))
      (node (ref "TIMER_555") (pin "3") (pinfunction "Q_3") (pintype "output"))
    )
    (net (code "82") (name "TX") (class "Default")
      (node (ref "TTL") (pin "4") (pinfunction "4_4") (pintype "passive"))
      (node (ref "U2") (pin "30") (pinfunction "PA9_30") (pintype "bidirectional"))
    )
    (net (code "83") (name "VB1") (class "Default")
      (node (ref "1") (pin "8") (pinfunction "VB_8") (pintype "power_in"))
      (node (ref "C8") (pin "1") (pinfunction "1_1") (pintype "passive"))
      (node (ref "D1") (pin "C") (pinfunction "C_C") (pintype "passive"))
      (node (ref "D3") (pin "C") (pinfunction "C_C") (pintype "passive"))
    )
    (net (code "84") (name "VB2") (class "Default")
      (node (ref "2") (pin "8") (pinfunction "VB_8") (pintype "power_in"))
      (node (ref "C11") (pin "1") (pinfunction "1_1") (pintype "passive"))
      (node (ref "D5") (pin "C") (pinfunction "C_C") (pintype "passive"))
      (node (ref "D6") (pin "C") (pinfunction "C_C") (pintype "passive"))
    )
    (net (code "85") (name "VBAT") (class "Default")
      (node (ref "U2") (pin "1") (pinfunction "VBAT_1") (pintype "bidirectional"))
    )
    (net (code "86") (name "VCC") (class "Default")
      (node (ref "1") (pin "5") (pinfunction "VCC_5") (pintype "power_in"))
      (node (ref "2") (pin "5") (pinfunction "VCC_5") (pintype "power_in"))
      (node (ref "7812") (pin "OUT") (pinfunction "OUT_OUT") (pintype "passive"))
      (node (ref "C12") (pin "1") (pinfunction "1_1") (pintype "passive"))
      (node (ref "C15") (pin "2") (pinfunction "2_2") (pintype "passive"))
      (node (ref "C22") (pin "1") (pinfunction "1_1") (pintype "passive"))
      (node (ref "C3") (pin "+") (pinfunction "+_+") (pintype "passive"))
      (node (ref "C9") (pin "1") (pinfunction "1_1") (pintype "passive"))
      (node (ref "D1") (pin "A") (pinfunction "A_A") (pintype "passive"))
      (node (ref "D5") (pin "A") (pinfunction "A_A") (pintype "passive"))
      (node (ref "PWR") (pin "A") (pinfunction "A_A") (pintype "passive"))
      (node (ref "R2") (pin "1") (pinfunction "1_1") (pintype "passive"))
      (node (ref "R20") (pin "1") (pinfunction "1_1") (pintype "passive"))
      (node (ref "R29") (pin "2") (pinfunction "2_2") (pintype "passive"))
      (node (ref "TIMER_555") (pin "4") (pinfunction "R_4") (pintype "input"))
      (node (ref "TIMER_555") (pin "8") (pinfunction "V+_8") (pintype "power_in"))
    )
    (net (code "87") (name "unconnected-(1-~{SD}-Pad2)") (class "Default")
      (node (ref "1") (pin "2") (pinfunction "~{SD}_2") (pintype "input"))
    )
    (net (code "88") (name "unconnected-(2-~{SD}-Pad2)") (class "Default")
      (node (ref "2") (pin "2") (pinfunction "~{SD}_2") (pintype "input"))
    )
  )
)
